# md2_redraw.net
KiCad netlist of a schematic drawn in EAGLE
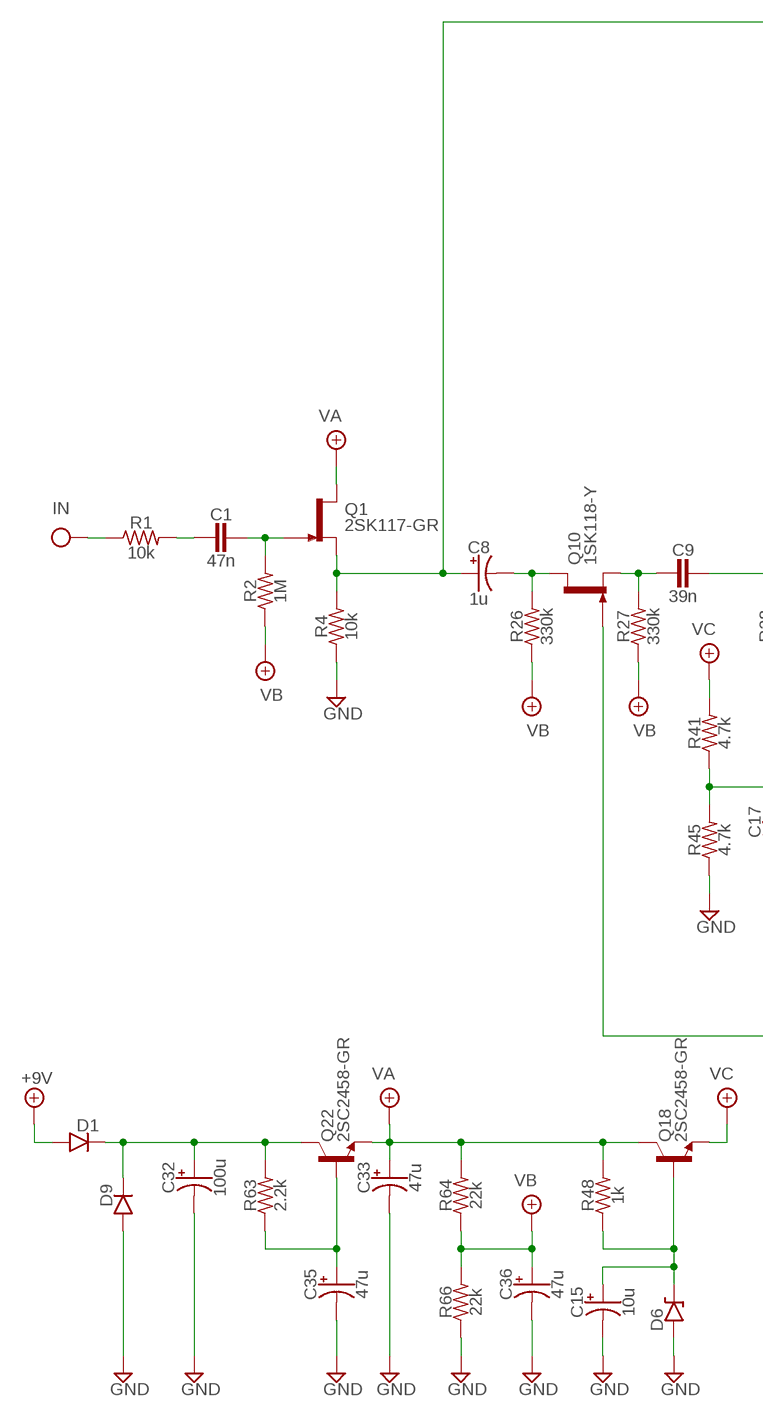
[diagram p0: schematic, sheet 1, part 1 of 2]
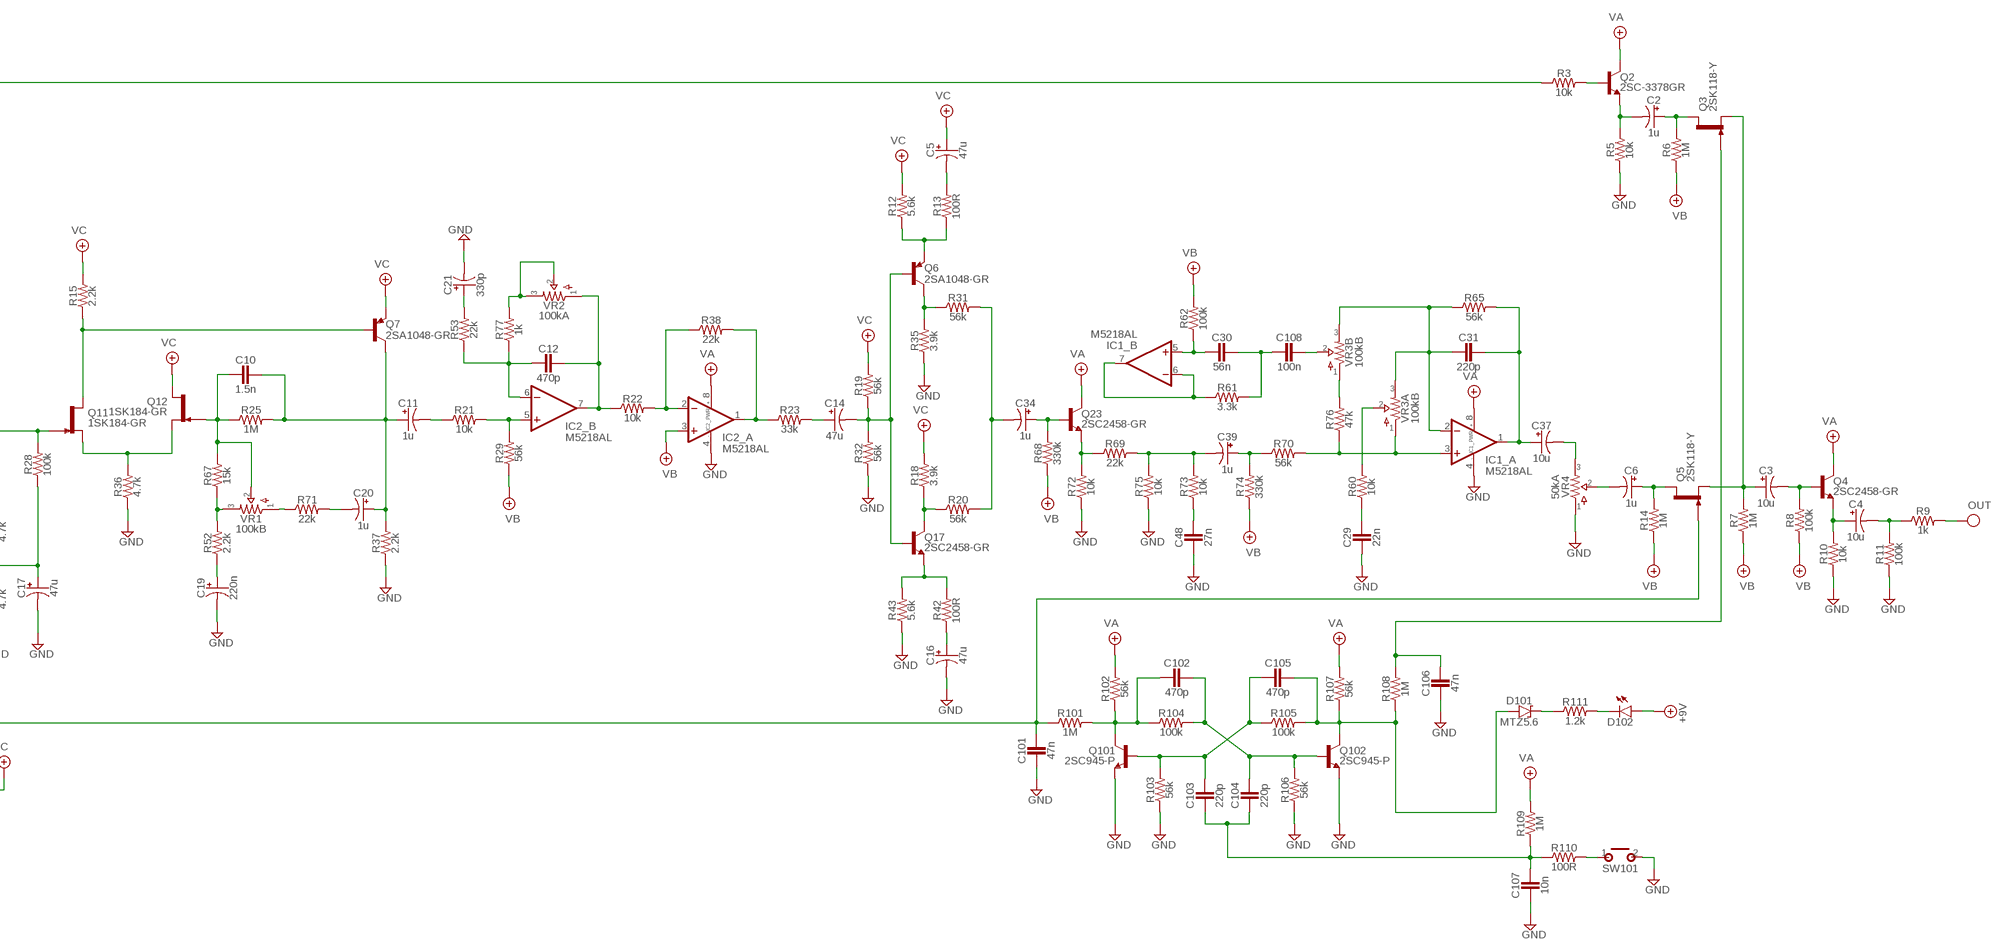
[diagram p1: schematic, sheet 1, part 2 of 2]

(export (version "E")
  (design (tool "Eeschema 10.0.6"))
  (components
    (comp (ref "C1")
      (value "47n")
      (footprint "eagle-import:BOX_SMALL")
      (libsource (lib "eagle-import") (part "CER/FILMBOX.1"))
    )
    (comp (ref "C2")
      (value "1u")
      (footprint "eagle-import:040_020")
      (libsource (lib "eagle-import") (part "0400"))
    )
    (comp (ref "C3")
      (value "10u")
      (footprint "eagle-import:040_020")
      (libsource (lib "eagle-import") (part "0400"))
    )
    (comp (ref "C4")
      (value "10u")
      (footprint "eagle-import:040_020")
      (libsource (lib "eagle-import") (part "0400"))
    )
    (comp (ref "C5")
      (value "47u")
      (footprint "eagle-import:040_020")
      (libsource (lib "eagle-import") (part "0400"))
    )
    (comp (ref "C6")
      (value "1u")
      (footprint "eagle-import:040_020")
      (libsource (lib "eagle-import") (part "0400"))
    )
    (comp (ref "C8")
      (value "1u")
      (footprint "eagle-import:040_020")
      (libsource (lib "eagle-import") (part "0400"))
    )
    (comp (ref "C9")
      (value "39n")
      (footprint "eagle-import:BOX_SMALL")
      (libsource (lib "eagle-import") (part "CER/FILMBOX.1"))
    )
    (comp (ref "C10")
      (value "1.5n")
      (footprint "eagle-import:BOX_SMALL")
      (libsource (lib "eagle-import") (part "CER/FILMBOX.1"))
    )
    (comp (ref "C11")
      (value "1u")
      (footprint "eagle-import:040_020")
      (libsource (lib "eagle-import") (part "0400"))
    )
    (comp (ref "C12")
      (value "470p")
      (footprint "eagle-import:BOX_SMALL")
      (libsource (lib "eagle-import") (part "CER/FILMBOX.1"))
    )
    (comp (ref "C14")
      (value "47u")
      (footprint "eagle-import:040_020")
      (libsource (lib "eagle-import") (part "0400"))
    )
    (comp (ref "C15")
      (value "10u")
      (footprint "eagle-import:040_020")
      (libsource (lib "eagle-import") (part "0400"))
    )
    (comp (ref "C16")
      (value "47u")
      (footprint "eagle-import:040_020")
      (libsource (lib "eagle-import") (part "0400"))
    )
    (comp (ref "C17")
      (value "47u")
      (footprint "eagle-import:040_020")
      (libsource (lib "eagle-import") (part "0400"))
    )
    (comp (ref "C19")
      (value "220n")
      (footprint "eagle-import:040_020")
      (libsource (lib "eagle-import") (part "0400"))
    )
    (comp (ref "C20")
      (value "1u")
      (footprint "eagle-import:040_020")
      (libsource (lib "eagle-import") (part "0400"))
    )
    (comp (ref "C21")
      (value "330p")
      (footprint "eagle-import:040_020")
      (libsource (lib "eagle-import") (part "0400"))
    )
    (comp (ref "C29")
      (value "22n")
      (footprint "eagle-import:BOX_SMALL")
      (libsource (lib "eagle-import") (part "CER/FILMBOX.1"))
    )
    (comp (ref "C30")
      (value "56n")
      (footprint "eagle-import:BOX_SMALL")
      (libsource (lib "eagle-import") (part "CER/FILMBOX.1"))
    )
    (comp (ref "C31")
      (value "220p")
      (footprint "eagle-import:BOX_SMALL")
      (libsource (lib "eagle-import") (part "CER/FILMBOX.1"))
    )
    (comp (ref "C32")
      (value "100u")
      (footprint "eagle-import:040_020")
      (libsource (lib "eagle-import") (part "0400"))
    )
    (comp (ref "C33")
      (value "47u")
      (footprint "eagle-import:040_020")
      (libsource (lib "eagle-import") (part "0400"))
    )
    (comp (ref "C34")
      (value "1u")
      (footprint "eagle-import:040_020")
      (libsource (lib "eagle-import") (part "0400"))
    )
    (comp (ref "C35")
      (value "47u")
      (footprint "eagle-import:040_020")
      (libsource (lib "eagle-import") (part "0400"))
    )
    (comp (ref "C36")
      (value "47u")
      (footprint "eagle-import:040_020")
      (libsource (lib "eagle-import") (part "0400"))
    )
    (comp (ref "C37")
      (value "10u")
      (footprint "eagle-import:040_020")
      (libsource (lib "eagle-import") (part "0400"))
    )
    (comp (ref "C39")
      (value "1u")
      (footprint "eagle-import:040_020")
      (libsource (lib "eagle-import") (part "0400"))
    )
    (comp (ref "C48")
      (value "27n")
      (footprint "eagle-import:BOX_SMALL")
      (libsource (lib "eagle-import") (part "CER/FILMBOX.1"))
    )
    (comp (ref "C101")
      (value "47n")
      (footprint "eagle-import:BOX_SMALL")
      (libsource (lib "eagle-import") (part "CER/FILMBOX.1"))
    )
    (comp (ref "C102")
      (value "470p")
      (footprint "eagle-import:BOX_SMALL")
      (libsource (lib "eagle-import") (part "CER/FILMBOX.1"))
    )
    (comp (ref "C103")
      (value "220p")
      (footprint "eagle-import:BOX_SMALL")
      (libsource (lib "eagle-import") (part "CER/FILMBOX.1"))
    )
    (comp (ref "C104")
      (value "220p")
      (footprint "eagle-import:BOX_SMALL")
      (libsource (lib "eagle-import") (part "CER/FILMBOX.1"))
    )
    (comp (ref "C105")
      (value "470p")
      (footprint "eagle-import:BOX_SMALL")
      (libsource (lib "eagle-import") (part "CER/FILMBOX.1"))
    )
    (comp (ref "C106")
      (value "47n")
      (footprint "eagle-import:BOX_SMALL")
      (libsource (lib "eagle-import") (part "CER/FILMBOX.1"))
    )
    (comp (ref "C107")
      (value "10n")
      (footprint "eagle-import:BOX_SMALL")
      (libsource (lib "eagle-import") (part "CER/FILMBOX.1"))
    )
    (comp (ref "C108")
      (value "100n")
      (footprint "eagle-import:BOX_SMALL")
      (libsource (lib "eagle-import") (part "CER/FILMBOX.1"))
    )
    (comp (ref "D1")
      (value "DO35.2")
      (footprint "eagle-import:DO35-2")
      (libsource (lib "eagle-import") (part "DO35.2"))
    )
    (comp (ref "D6")
      (value "ZENER.2")
      (footprint "eagle-import:DO41-2")
      (libsource (lib "eagle-import") (part "ZENER.2"))
    )
    (comp (ref "D9")
      (value "DO35.2")
      (footprint "eagle-import:DO35-2")
      (libsource (lib "eagle-import") (part "DO35.2"))
    )
    (comp (ref "D101")
      (value "MTZ5.6")
      (footprint "eagle-import:DO41-2")
      (libsource (lib "eagle-import") (part "ZENER.2"))
    )
    (comp (ref "D102")
      (value "LED")
      (footprint "eagle-import:3MM_D")
      (libsource (lib "eagle-import") (part "LED"))
    )
    (comp (ref "IC1")
      (value "M5218AL")
      (footprint "eagle-import:DIL0")
      (libsource (lib "eagle-import") (part "DUALTH"))
    )
    (comp (ref "IC2")
      (value "M5218AL")
      (footprint "eagle-import:DIL0")
      (libsource (lib "eagle-import") (part "DUALTH"))
    )
    (comp (ref "Q1")
      (value "2SK117-GR")
      (footprint "eagle-import:TO92-")
      (libsource (lib "eagle-import") (part "2N3819TO-92S"))
    )
    (comp (ref "Q2")
      (value "2SC-3378GR")
      (footprint "eagle-import:TO92-")
      (libsource (lib "eagle-import") (part "2SC828A"))
    )
    (comp (ref "Q3")
      (value "2SK118-Y")
      (footprint "eagle-import:TO92-")
      (libsource (lib "eagle-import") (part "2N3819TO-92S"))
    )
    (comp (ref "Q4")
      (value "2SC2458-GR")
      (footprint "eagle-import:TO92-")
      (libsource (lib "eagle-import") (part "2SC828A"))
    )
    (comp (ref "Q5")
      (value "2SK118-Y")
      (footprint "eagle-import:TO92-")
      (libsource (lib "eagle-import") (part "2N3819TO-92S"))
    )
    (comp (ref "Q6")
      (value "2SA1048-GR")
      (footprint "eagle-import:TO92")
      (libsource (lib "eagle-import") (part "2N3906"))
    )
    (comp (ref "Q7")
      (value "2SA1048-GR")
      (footprint "eagle-import:TO92")
      (libsource (lib "eagle-import") (part "2N3906"))
    )
    (comp (ref "Q10")
      (value "1SK118-Y")
      (footprint "eagle-import:TO92-")
      (libsource (lib "eagle-import") (part "2N3819TO-92S"))
    )
    (comp (ref "Q11")
      (value "1SK184-GR")
      (footprint "eagle-import:TO92-")
      (libsource (lib "eagle-import") (part "2N3819TO-92S"))
    )
    (comp (ref "Q12")
      (value "1SK184-GR")
      (footprint "eagle-import:TO92-")
      (libsource (lib "eagle-import") (part "2N3819TO-92S"))
    )
    (comp (ref "Q17")
      (value "2SC2458-GR")
      (footprint "eagle-import:TO92-")
      (libsource (lib "eagle-import") (part "2N3904"))
    )
    (comp (ref "Q18")
      (value "2SC2458-GR")
      (footprint "eagle-import:TO92-")
      (libsource (lib "eagle-import") (part "2SC828A"))
    )
    (comp (ref "Q22")
      (value "2SC2458-GR")
      (footprint "eagle-import:TO92-")
      (libsource (lib "eagle-import") (part "2SC828A"))
    )
    (comp (ref "Q23")
      (value "2SC2458-GR")
      (footprint "eagle-import:TO92-")
      (libsource (lib "eagle-import") (part "2N3904"))
    )
    (comp (ref "Q101")
      (value "2SC945-P")
      (footprint "eagle-import:TO92-")
      (libsource (lib "eagle-import") (part "2SC828A"))
    )
    (comp (ref "Q102")
      (value "2SC945-P")
      (footprint "eagle-import:TO92-")
      (libsource (lib "eagle-import") (part "2SC828A"))
    )
    (comp (ref "R1")
      (value "10k")
      (footprint "eagle-import:R0207_3")
      (libsource (lib "eagle-import") (part "R_.3B"))
    )
    (comp (ref "R2")
      (value "1M")
      (footprint "eagle-import:R0207_3")
      (libsource (lib "eagle-import") (part "R_.3B"))
    )
    (comp (ref "R3")
      (value "10k")
      (footprint "eagle-import:R0207_3")
      (libsource (lib "eagle-import") (part "R_.3B"))
    )
    (comp (ref "R4")
      (value "10k")
      (footprint "eagle-import:R0207_3")
      (libsource (lib "eagle-import") (part "R_.3B"))
    )
    (comp (ref "R5")
      (value "10k")
      (footprint "eagle-import:R0207_3")
      (libsource (lib "eagle-import") (part "R_.3B"))
    )
    (comp (ref "R6")
      (value "1M")
      (footprint "eagle-import:R0207_3")
      (libsource (lib "eagle-import") (part "R_.3B"))
    )
    (comp (ref "R7")
      (value "1M")
      (footprint "eagle-import:R0207_3")
      (libsource (lib "eagle-import") (part "R_.3B"))
    )
    (comp (ref "R8")
      (value "100k")
      (footprint "eagle-import:R0207_3")
      (libsource (lib "eagle-import") (part "R_.3B"))
    )
    (comp (ref "R9")
      (value "1k")
      (footprint "eagle-import:R0207_3")
      (libsource (lib "eagle-import") (part "R_.3B"))
    )
    (comp (ref "R10")
      (value "10k")
      (footprint "eagle-import:R0207_3")
      (libsource (lib "eagle-import") (part "R_.3B"))
    )
    (comp (ref "R11")
      (value "100k")
      (footprint "eagle-import:R0207_3")
      (libsource (lib "eagle-import") (part "R_.3B"))
    )
    (comp (ref "R12")
      (value "5.6k")
      (footprint "eagle-import:R0207_3")
      (libsource (lib "eagle-import") (part "R_.3B"))
    )
    (comp (ref "R13")
      (value "100R")
      (footprint "eagle-import:R0207_3")
      (libsource (lib "eagle-import") (part "R_.3B"))
    )
    (comp (ref "R14")
      (value "1M")
      (footprint "eagle-import:R0207_3")
      (libsource (lib "eagle-import") (part "R_.3B"))
    )
    (comp (ref "R15")
      (value "2.2k")
      (footprint "eagle-import:R0207_3")
      (libsource (lib "eagle-import") (part "R_.3B"))
    )
    (comp (ref "R18")
      (value "3.9k")
      (footprint "eagle-import:R0207_3")
      (libsource (lib "eagle-import") (part "R_.3B"))
    )
    (comp (ref "R19")
      (value "56k")
      (footprint "eagle-import:R0207_3")
      (libsource (lib "eagle-import") (part "R_.3B"))
    )
    (comp (ref "R20")
      (value "56k")
      (footprint "eagle-import:R0207_3")
      (libsource (lib "eagle-import") (part "R_.3B"))
    )
    (comp (ref "R21")
      (value "10k")
      (footprint "eagle-import:R0207_3")
      (libsource (lib "eagle-import") (part "R_.3B"))
    )
    (comp (ref "R22")
      (value "10k")
      (footprint "eagle-import:R0207_3")
      (libsource (lib "eagle-import") (part "R_.3B"))
    )
    (comp (ref "R23")
      (value "33k")
      (footprint "eagle-import:R0207_3")
      (libsource (lib "eagle-import") (part "R_.3B"))
    )
    (comp (ref "R25")
      (value "1M")
      (footprint "eagle-import:R0207_3")
      (libsource (lib "eagle-import") (part "R_.3B"))
    )
    (comp (ref "R26")
      (value "330k")
      (footprint "eagle-import:R0207_3")
      (libsource (lib "eagle-import") (part "R_.3B"))
    )
    (comp (ref "R27")
      (value "330k")
      (footprint "eagle-import:R0207_3")
      (libsource (lib "eagle-import") (part "R_.3B"))
    )
    (comp (ref "R28")
      (value "100k")
      (footprint "eagle-import:R0207_3")
      (libsource (lib "eagle-import") (part "R_.3B"))
    )
    (comp (ref "R29")
      (value "56k")
      (footprint "eagle-import:R0207_3")
      (libsource (lib "eagle-import") (part "R_.3B"))
    )
    (comp (ref "R31")
      (value "56k")
      (footprint "eagle-import:R0207_3")
      (libsource (lib "eagle-import") (part "R_.3B"))
    )
    (comp (ref "R32")
      (value "56k")
      (footprint "eagle-import:R0207_3")
      (libsource (lib "eagle-import") (part "R_.3B"))
    )
    (comp (ref "R35")
      (value "3.9k")
      (footprint "eagle-import:R0207_3")
      (libsource (lib "eagle-import") (part "R_.3B"))
    )
    (comp (ref "R36")
      (value "4.7k")
      (footprint "eagle-import:R0207_3")
      (libsource (lib "eagle-import") (part "R_.3B"))
    )
    (comp (ref "R37")
      (value "2.2k")
      (footprint "eagle-import:R0207_3")
      (libsource (lib "eagle-import") (part "R_.3B"))
    )
    (comp (ref "R38")
      (value "22k")
      (footprint "eagle-import:R0207_3")
      (libsource (lib "eagle-import") (part "R_.3B"))
    )
    (comp (ref "R41")
      (value "4.7k")
      (footprint "eagle-import:R0207_3")
      (libsource (lib "eagle-import") (part "R_.3B"))
    )
    (comp (ref "R42")
      (value "100R")
      (footprint "eagle-import:R0207_3")
      (libsource (lib "eagle-import") (part "R_.3B"))
    )
    (comp (ref "R43")
      (value "5.6k")
      (footprint "eagle-import:R0207_3")
      (libsource (lib "eagle-import") (part "R_.3B"))
    )
    (comp (ref "R45")
      (value "4.7k")
      (footprint "eagle-import:R0207_3")
      (libsource (lib "eagle-import") (part "R_.3B"))
    )
    (comp (ref "R48")
      (value "1k")
      (footprint "eagle-import:R0207_3")
      (libsource (lib "eagle-import") (part "R_.3B"))
    )
    (comp (ref "R52")
      (value "2.2k")
      (footprint "eagle-import:R0207_3")
      (libsource (lib "eagle-import") (part "R_.3B"))
    )
    (comp (ref "R53")
      (value "22k")
      (footprint "eagle-import:R0207_3")
      (libsource (lib "eagle-import") (part "R_.3B"))
    )
    (comp (ref "R60")
      (value "10k")
      (footprint "eagle-import:R0207_3")
      (libsource (lib "eagle-import") (part "R_.3B"))
    )
    (comp (ref "R61")
      (value "3.3k")
      (footprint "eagle-import:R0207_3")
      (libsource (lib "eagle-import") (part "R_.3B"))
    )
    (comp (ref "R62")
      (value "100k")
      (footprint "eagle-import:R0207_3")
      (libsource (lib "eagle-import") (part "R_.3B"))
    )
    (comp (ref "R63")
      (value "2.2k")
      (footprint "eagle-import:R0207_3")
      (libsource (lib "eagle-import") (part "R_.3B"))
    )
    (comp (ref "R64")
      (value "22k")
      (footprint "eagle-import:R0207_3")
      (libsource (lib "eagle-import") (part "R_.3B"))
    )
    (comp (ref "R65")
      (value "56k")
      (footprint "eagle-import:R0207_3")
      (libsource (lib "eagle-import") (part "R_.3B"))
    )
    (comp (ref "R66")
      (value "22k")
      (footprint "eagle-import:R0207_3")
      (libsource (lib "eagle-import") (part "R_.3B"))
    )
    (comp (ref "R67")
      (value "15k")
      (footprint "eagle-import:R0207_3")
      (libsource (lib "eagle-import") (part "R_.3B"))
    )
    (comp (ref "R68")
      (value "330k")
      (footprint "eagle-import:R0207_3")
      (libsource (lib "eagle-import") (part "R_.3B"))
    )
    (comp (ref "R69")
      (value "22k")
      (footprint "eagle-import:R0207_3")
      (libsource (lib "eagle-import") (part "R_.3B"))
    )
    (comp (ref "R70")
      (value "56k")
      (footprint "eagle-import:R0207_3")
      (libsource (lib "eagle-import") (part "R_.3B"))
    )
    (comp (ref "R71")
      (value "22k")
      (footprint "eagle-import:R0207_3")
      (libsource (lib "eagle-import") (part "R_.3B"))
    )
    (comp (ref "R72")
      (value "10k")
      (footprint "eagle-import:R0207_3")
      (libsource (lib "eagle-import") (part "R_.3B"))
    )
    (comp (ref "R73")
      (value "10k")
      (footprint "eagle-import:R0207_3")
      (libsource (lib "eagle-import") (part "R_.3B"))
    )
    (comp (ref "R74")
      (value "330k")
      (footprint "eagle-import:R0207_3")
      (libsource (lib "eagle-import") (part "R_.3B"))
    )
    (comp (ref "R75")
      (value "10k")
      (footprint "eagle-import:R0207_3")
      (libsource (lib "eagle-import") (part "R_.3B"))
    )
    (comp (ref "R76")
      (value "47k")
      (footprint "eagle-import:R0207_3")
      (libsource (lib "eagle-import") (part "R_.3B"))
    )
    (comp (ref "R77")
      (value "1k")
      (footprint "eagle-import:R0207_3")
      (libsource (lib "eagle-import") (part "R_.3B"))
    )
    (comp (ref "R101")
      (value "1M")
      (footprint "eagle-import:R0207_3")
      (libsource (lib "eagle-import") (part "R_.3B"))
    )
    (comp (ref "R102")
      (value "56k")
      (footprint "eagle-import:R0207_3")
      (libsource (lib "eagle-import") (part "R_.3B"))
    )
    (comp (ref "R103")
      (value "56k")
      (footprint "eagle-import:R0207_3")
      (libsource (lib "eagle-import") (part "R_.3B"))
    )
    (comp (ref "R104")
      (value "100k")
      (footprint "eagle-import:R0207_3")
      (libsource (lib "eagle-import") (part "R_.3B"))
    )
    (comp (ref "R105")
      (value "100k")
      (footprint "eagle-import:R0207_3")
      (libsource (lib "eagle-import") (part "R_.3B"))
    )
    (comp (ref "R106")
      (value "56k")
      (footprint "eagle-import:R0207_3")
      (libsource (lib "eagle-import") (part "R_.3B"))
    )
    (comp (ref "R107")
      (value "56k")
      (footprint "eagle-import:R0207_3")
      (libsource (lib "eagle-import") (part "R_.3B"))
    )
    (comp (ref "R108")
      (value "1M")
      (footprint "eagle-import:R0207_3")
      (libsource (lib "eagle-import") (part "R_.3B"))
    )
    (comp (ref "R109")
      (value "1M")
      (footprint "eagle-import:R0207_3")
      (libsource (lib "eagle-import") (part "R_.3B"))
    )
    (comp (ref "R110")
      (value "100R")
      (footprint "eagle-import:R0207_3")
      (libsource (lib "eagle-import") (part "R_.3B"))
    )
    (comp (ref "R111")
      (value "1.2k")
      (footprint "eagle-import:R0207_3")
      (libsource (lib "eagle-import") (part "R_.3B"))
    )
    (comp (ref "SW101")
      (value "MOMENTARY")
      (footprint "eagle-import:SPST")
      (libsource (lib "eagle-import") (part "MOMENTARY"))
    )
    (comp (ref "VR1")
      (value "100kB")
      (footprint "eagle-import:16MM")
      (libsource (lib "eagle-import") (part "POTS16MM"))
    )
    (comp (ref "VR2")
      (value "100kA")
      (footprint "eagle-import:16MM")
      (libsource (lib "eagle-import") (part "POTS16MM"))
    )
    (comp (ref "VR3A")
      (value "100kB")
      (footprint "eagle-import:16MM")
      (libsource (lib "eagle-import") (part "POTS16MM"))
    )
    (comp (ref "VR3B")
      (value "100kB")
      (footprint "eagle-import:16MM")
      (libsource (lib "eagle-import") (part "POTS16MM"))
    )
    (comp (ref "VR4")
      (value "50kA")
      (footprint "eagle-import:16MM")
      (libsource (lib "eagle-import") (part "POTS16MM"))
    )
  )
  (nets
    (net (code "1") (name "+9V") (class "Default")
      (node (ref "D1") (pin "A") (pinfunction "A_A") (pintype "passive"))
      (node (ref "D102") (pin "ANODE") (pinfunction "A_ANODE") (pintype "passive"))
    )
    (net (code "2") (name "GND") (class "Default")
      (node (ref "C101") (pin "2") (pinfunction "2_2") (pintype "passive"))
      (node (ref "C106") (pin "2") (pinfunction "2_2") (pintype "passive"))
      (node (ref "C107") (pin "2") (pinfunction "2_2") (pintype "passive"))
      (node (ref "C15") (pin "-") (pinfunction "-_-") (pintype "passive"))
      (node (ref "C16") (pin "-") (pinfunction "-_-") (pintype "passive"))
      (node (ref "C17") (pin "-") (pinfunction "-_-") (pintype "passive"))
      (node (ref "C19") (pin "-") (pinfunction "-_-") (pintype "passive"))
      (node (ref "C21") (pin "-") (pinfunction "-_-") (pintype "passive"))
      (node (ref "C29") (pin "2") (pinfunction "2_2") (pintype "passive"))
      (node (ref "C32") (pin "-") (pinfunction "-_-") (pintype "passive"))
      (node (ref "C33") (pin "-") (pinfunction "-_-") (pintype "passive"))
      (node (ref "C35") (pin "-") (pinfunction "-_-") (pintype "passive"))
      (node (ref "C36") (pin "-") (pinfunction "-_-") (pintype "passive"))
      (node (ref "C48") (pin "2") (pinfunction "2_2") (pintype "passive"))
      (node (ref "D6") (pin "A") (pinfunction "A_A") (pintype "passive"))
      (node (ref "D9") (pin "A") (pinfunction "A_A") (pintype "passive"))
      (node (ref "IC1") (pin "4") (pinfunction "V-_4") (pintype "power_in"))
      (node (ref "IC2") (pin "4") (pinfunction "V-_4") (pintype "power_in"))
      (node (ref "Q101") (pin "3") (pinfunction "E_3") (pintype "passive"))
      (node (ref "Q102") (pin "3") (pinfunction "E_3") (pintype "passive"))
      (node (ref "R10") (pin "1") (pinfunction "1_1") (pintype "passive"))
      (node (ref "R103") (pin "1") (pinfunction "1_1") (pintype "passive"))
      (node (ref "R106") (pin "1") (pinfunction "1_1") (pintype "passive"))
      (node (ref "R11") (pin "1") (pinfunction "1_1") (pintype "passive"))
      (node (ref "R32") (pin "1") (pinfunction "1_1") (pintype "passive"))
      (node (ref "R35") (pin "1") (pinfunction "1_1") (pintype "passive"))
      (node (ref "R36") (pin "1") (pinfunction "1_1") (pintype "passive"))
      (node (ref "R37") (pin "1") (pinfunction "1_1") (pintype "passive"))
      (node (ref "R4") (pin "1") (pinfunction "1_1") (pintype "passive"))
      (node (ref "R43") (pin "1") (pinfunction "1_1") (pintype "passive"))
      (node (ref "R45") (pin "1") (pinfunction "1_1") (pintype "passive"))
      (node (ref "R5") (pin "1") (pinfunction "1_1") (pintype "passive"))
      (node (ref "R66") (pin "1") (pinfunction "1_1") (pintype "passive"))
      (node (ref "R72") (pin "1") (pinfunction "1_1") (pintype "passive"))
      (node (ref "R75") (pin "1") (pinfunction "1_1") (pintype "passive"))
      (node (ref "SW101") (pin "2") (pinfunction "S_2") (pintype "passive"))
      (node (ref "VR4") (pin "1") (pinfunction "1_1") (pintype "passive"))
    )
    (net (code "3") (name "IN") (class "Default")
      (node (ref "R1") (pin "1") (pinfunction "1_1") (pintype "passive"))
    )
    (net (code "4") (name "Net-(C1-Pad2)") (class "Default")
      (node (ref "C1") (pin "2") (pinfunction "2_2") (pintype "passive"))
      (node (ref "R1") (pin "2") (pinfunction "2_2") (pintype "passive"))
    )
    (net (code "5") (name "Net-(C4-Pad-)") (class "Default")
      (node (ref "C4") (pin "-") (pinfunction "-_-") (pintype "passive"))
      (node (ref "R11") (pin "2") (pinfunction "2_2") (pintype "passive"))
      (node (ref "R9") (pin "1") (pinfunction "1_1") (pintype "passive"))
    )
    (net (code "6") (name "Net-(C5-Pad-)") (class "Default")
      (node (ref "C5") (pin "-") (pinfunction "-_-") (pintype "passive"))
      (node (ref "R13") (pin "2") (pinfunction "2_2") (pintype "passive"))
    )
    (net (code "7") (name "Net-(C6-Pad-)") (class "Default")
      (node (ref "C6") (pin "-") (pinfunction "-_-") (pintype "passive"))
      (node (ref "VR4") (pin "2") (pinfunction "2_2") (pintype "passive"))
    )
    (net (code "8") (name "Net-(C11-Pad-)") (class "Default")
      (node (ref "C11") (pin "-") (pinfunction "-_-") (pintype "passive"))
      (node (ref "R21") (pin "1") (pinfunction "1_1") (pintype "passive"))
    )
    (net (code "9") (name "Net-(C14-Pad+)") (class "Default")
      (node (ref "C14") (pin "+") (pinfunction "+_+") (pintype "passive"))
      (node (ref "R23") (pin "2") (pinfunction "2_2") (pintype "passive"))
    )
    (net (code "10") (name "Net-(C16-Pad+)") (class "Default")
      (node (ref "C16") (pin "+") (pinfunction "+_+") (pintype "passive"))
      (node (ref "R42") (pin "1") (pinfunction "1_1") (pintype "passive"))
    )
    (net (code "11") (name "Net-(C17-Pad+)") (class "Default")
      (node (ref "C17") (pin "+") (pinfunction "+_+") (pintype "passive"))
      (node (ref "R28") (pin "1") (pinfunction "1_1") (pintype "passive"))
      (node (ref "R41") (pin "1") (pinfunction "1_1") (pintype "passive"))
      (node (ref "R45") (pin "2") (pinfunction "2_2") (pintype "passive"))
    )
    (net (code "12") (name "Net-(C19-Pad+)") (class "Default")
      (node (ref "C19") (pin "+") (pinfunction "+_+") (pintype "passive"))
      (node (ref "R52") (pin "1") (pinfunction "1_1") (pintype "passive"))
    )
    (net (code "13") (name "Net-(C20-Pad-)") (class "Default")
      (node (ref "C20") (pin "-") (pinfunction "-_-") (pintype "passive"))
      (node (ref "R71") (pin "2") (pinfunction "2_2") (pintype "passive"))
    )
    (net (code "14") (name "Net-(C21-Pad+)") (class "Default")
      (node (ref "C21") (pin "+") (pinfunction "+_+") (pintype "passive"))
      (node (ref "R53") (pin "2") (pinfunction "2_2") (pintype "passive"))
    )
    (net (code "15") (name "Net-(C29-Pad1)") (class "Default")
      (node (ref "C29") (pin "1") (pinfunction "1_1") (pintype "passive"))
      (node (ref "R60") (pin "1") (pinfunction "1_1") (pintype "passive"))
    )
    (net (code "16") (name "Net-(C34-Pad-)") (class "Default")
      (node (ref "C34") (pin "-") (pinfunction "-_-") (pintype "passive"))
      (node (ref "R20") (pin "2") (pinfunction "2_2") (pintype "passive"))
      (node (ref "R31") (pin "2") (pinfunction "2_2") (pintype "passive"))
    )
    (net (code "17") (name "Net-(C37-Pad-)") (class "Default")
      (node (ref "C37") (pin "-") (pinfunction "-_-") (pintype "passive"))
      (node (ref "VR4") (pin "3") (pinfunction "3_3") (pintype "passive"))
    )
    (net (code "18") (name "Net-(C39-Pad+)") (class "Default")
      (node (ref "C39") (pin "+") (pinfunction "+_+") (pintype "passive"))
      (node (ref "R70") (pin "1") (pinfunction "1_1") (pintype "passive"))
      (node (ref "R74") (pin "2") (pinfunction "2_2") (pintype "passive"))
    )
    (net (code "19") (name "Net-(C39-Pad-)") (class "Default")
      (node (ref "C39") (pin "-") (pinfunction "-_-") (pintype "passive"))
      (node (ref "R69") (pin "2") (pinfunction "2_2") (pintype "passive"))
      (node (ref "R73") (pin "2") (pinfunction "2_2") (pintype "passive"))
      (node (ref "R75") (pin "2") (pinfunction "2_2") (pintype "passive"))
    )
    (net (code "20") (name "Net-(C48-Pad1)") (class "Default")
      (node (ref "C48") (pin "1") (pinfunction "1_1") (pintype "passive"))
      (node (ref "R73") (pin "1") (pinfunction "1_1") (pintype "passive"))
    )
    (net (code "21") (name "Net-(C103-Pad2)") (class "Default")
      (node (ref "C103") (pin "2") (pinfunction "2_2") (pintype "passive"))
      (node (ref "C104") (pin "2") (pinfunction "2_2") (pintype "passive"))
      (node (ref "C107") (pin "1") (pinfunction "1_1") (pintype "passive"))
      (node (ref "R109") (pin "1") (pinfunction "1_1") (pintype "passive"))
      (node (ref "R110") (pin "1") (pinfunction "1_1") (pintype "passive"))
    )
    (net (code "22") (name "Net-(C108-Pad1)") (class "Default")
      (node (ref "C108") (pin "1") (pinfunction "1_1") (pintype "passive"))
      (node (ref "VR3B") (pin "2") (pinfunction "2_2") (pintype "passive"))
    )
    (net (code "23") (name "Net-(C108-Pad2)") (class "Default")
      (node (ref "C108") (pin "2") (pinfunction "2_2") (pintype "passive"))
      (node (ref "C30") (pin "1") (pinfunction "1_1") (pintype "passive"))
      (node (ref "R61") (pin "2") (pinfunction "2_2") (pintype "passive"))
    )
    (net (code "24") (name "Net-(D101-PadC)") (class "Default")
      (node (ref "D101") (pin "C") (pinfunction "C_C") (pintype "passive"))
      (node (ref "R111") (pin "1") (pinfunction "1_1") (pintype "passive"))
    )
    (net (code "25") (name "Net-(D102-C)") (class "Default")
      (node (ref "D102") (pin "P$1") (pinfunction "C_P$1") (pintype "passive"))
      (node (ref "R111") (pin "2") (pinfunction "2_2") (pintype "passive"))
    )
    (net (code "26") (name "Net-(IC1A-+IN)") (class "Default")
      (node (ref "IC1") (pin "3") (pinfunction "+IN_3") (pintype "input"))
      (node (ref "R70") (pin "2") (pinfunction "2_2") (pintype "passive"))
      (node (ref "R76") (pin "1") (pinfunction "1_1") (pintype "passive"))
      (node (ref "VR3A") (pin "1") (pinfunction "1_1") (pintype "passive"))
    )
    (net (code "27") (name "Net-(IC1A--IN)") (class "Default")
      (node (ref "C31") (pin "2") (pinfunction "2_2") (pintype "passive"))
      (node (ref "IC1") (pin "2") (pinfunction "-IN_2") (pintype "input"))
      (node (ref "R65") (pin "1") (pinfunction "1_1") (pintype "passive"))
      (node (ref "VR3A") (pin "3") (pinfunction "3_3") (pintype "passive"))
      (node (ref "VR3B") (pin "3") (pinfunction "3_3") (pintype "passive"))
    )
    (net (code "28") (name "Net-(IC1A-OUT)") (class "Default")
      (node (ref "C31") (pin "1") (pinfunction "1_1") (pintype "passive"))
      (node (ref "C37") (pin "+") (pinfunction "+_+") (pintype "passive"))
      (node (ref "IC1") (pin "1") (pinfunction "OUT_1") (pintype "output"))
      (node (ref "R65") (pin "2") (pinfunction "2_2") (pintype "passive"))
    )
    (net (code "29") (name "Net-(IC1B-+IN)") (class "Default")
      (node (ref "C30") (pin "2") (pinfunction "2_2") (pintype "passive"))
      (node (ref "IC1") (pin "5") (pinfunction "+IN_5") (pintype "input"))
      (node (ref "R62") (pin "1") (pinfunction "1_1") (pintype "passive"))
    )
    (net (code "30") (name "Net-(IC1B--IN)") (class "Default")
      (node (ref "IC1") (pin "6") (pinfunction "-IN_6") (pintype "input"))
      (node (ref "IC1") (pin "7") (pinfunction "OUT_7") (pintype "output"))
      (node (ref "R61") (pin "1") (pinfunction "1_1") (pintype "passive"))
    )
    (net (code "31") (name "Net-(IC2A--IN)") (class "Default")
      (node (ref "IC2") (pin "2") (pinfunction "-IN_2") (pintype "input"))
      (node (ref "R22") (pin "2") (pinfunction "2_2") (pintype "passive"))
      (node (ref "R38") (pin "1") (pinfunction "1_1") (pintype "passive"))
    )
    (net (code "32") (name "Net-(IC2A-OUT)") (class "Default")
      (node (ref "IC2") (pin "1") (pinfunction "OUT_1") (pintype "output"))
      (node (ref "R23") (pin "1") (pinfunction "1_1") (pintype "passive"))
      (node (ref "R38") (pin "2") (pinfunction "2_2") (pintype "passive"))
    )
    (net (code "33") (name "Net-(IC2B-+IN)") (class "Default")
      (node (ref "IC2") (pin "5") (pinfunction "+IN_5") (pintype "input"))
      (node (ref "R21") (pin "2") (pinfunction "2_2") (pintype "passive"))
      (node (ref "R29") (pin "2") (pinfunction "2_2") (pintype "passive"))
    )
    (net (code "34") (name "Net-(IC2B--IN)") (class "Default")
      (node (ref "C12") (pin "2") (pinfunction "2_2") (pintype "passive"))
      (node (ref "IC2") (pin "6") (pinfunction "-IN_6") (pintype "input"))
      (node (ref "R53") (pin "1") (pinfunction "1_1") (pintype "passive"))
      (node (ref "R77") (pin "1") (pinfunction "1_1") (pintype "passive"))
    )
    (net (code "35") (name "Net-(IC2B-OUT)") (class "Default")
      (node (ref "C12") (pin "1") (pinfunction "1_1") (pintype "passive"))
      (node (ref "IC2") (pin "7") (pinfunction "OUT_7") (pintype "output"))
      (node (ref "R22") (pin "1") (pinfunction "1_1") (pintype "passive"))
      (node (ref "VR2") (pin "1") (pinfunction "1_1") (pintype "passive"))
    )
    (net (code "36") (name "Net-(Q1-G)") (class "Default")
      (node (ref "C1") (pin "1") (pinfunction "1_1") (pintype "passive"))
      (node (ref "Q1") (pin "2") (pinfunction "G_2") (pintype "passive"))
      (node (ref "R2") (pin "2") (pinfunction "2_2") (pintype "passive"))
    )
    (net (code "37") (name "Net-(Q1-S)") (class "Default")
      (node (ref "C8") (pin "+") (pinfunction "+_+") (pintype "passive"))
      (node (ref "Q1") (pin "1") (pinfunction "S_1") (pintype "passive"))
      (node (ref "R3") (pin "1") (pinfunction "1_1") (pintype "passive"))
      (node (ref "R4") (pin "2") (pinfunction "2_2") (pintype "passive"))
    )
    (net (code "38") (name "Net-(Q2-B)") (class "Default")
      (node (ref "Q2") (pin "1") (pinfunction "B_1") (pintype "passive"))
      (node (ref "R3") (pin "2") (pinfunction "2_2") (pintype "passive"))
    )
    (net (code "39") (name "Net-(Q2-E)") (class "Default")
      (node (ref "C2") (pin "-") (pinfunction "-_-") (pintype "passive"))
      (node (ref "Q2") (pin "3") (pinfunction "E_3") (pintype "passive"))
      (node (ref "R5") (pin "2") (pinfunction "2_2") (pintype "passive"))
    )
    (net (code "40") (name "Net-(Q3-D)") (class "Default")
      (node (ref "C2") (pin "+") (pinfunction "+_+") (pintype "passive"))
      (node (ref "Q3") (pin "3") (pinfunction "D_3") (pintype "passive"))
      (node (ref "R6") (pin "2") (pinfunction "2_2") (pintype "passive"))
    )
    (net (code "41") (name "Net-(Q3-G)") (class "Default")
      (node (ref "C106") (pin "1") (pinfunction "1_1") (pintype "passive"))
      (node (ref "Q3") (pin "2") (pinfunction "G_2") (pintype "passive"))
      (node (ref "R108") (pin "2") (pinfunction "2_2") (pintype "passive"))
    )
    (net (code "42") (name "Net-(Q3-S)") (class "Default")
      (node (ref "C3") (pin "+") (pinfunction "+_+") (pintype "passive"))
      (node (ref "Q3") (pin "1") (pinfunction "S_1") (pintype "passive"))
      (node (ref "Q5") (pin "1") (pinfunction "S_1") (pintype "passive"))
      (node (ref "R7") (pin "2") (pinfunction "2_2") (pintype "passive"))
    )
    (net (code "43") (name "Net-(Q4-B)") (class "Default")
      (node (ref "C3") (pin "-") (pinfunction "-_-") (pintype "passive"))
      (node (ref "Q4") (pin "1") (pinfunction "B_1") (pintype "passive"))
      (node (ref "R8") (pin "2") (pinfunction "2_2") (pintype "passive"))
    )
    (net (code "44") (name "Net-(Q4-E)") (class "Default")
      (node (ref "C4") (pin "+") (pinfunction "+_+") (pintype "passive"))
      (node (ref "Q4") (pin "3") (pinfunction "E_3") (pintype "passive"))
      (node (ref "R10") (pin "2") (pinfunction "2_2") (pintype "passive"))
    )
    (net (code "45") (name "Net-(Q5-D)") (class "Default")
      (node (ref "C6") (pin "+") (pinfunction "+_+") (pintype "passive"))
      (node (ref "Q5") (pin "3") (pinfunction "D_3") (pintype "passive"))
      (node (ref "R14") (pin "2") (pinfunction "2_2") (pintype "passive"))
    )
    (net (code "46") (name "Net-(Q6-C)") (class "Default")
      (node (ref "Q6") (pin "1") (pinfunction "C_1") (pintype "passive"))
      (node (ref "R31") (pin "1") (pinfunction "1_1") (pintype "passive"))
      (node (ref "R35") (pin "2") (pinfunction "2_2") (pintype "passive"))
    )
    (net (code "47") (name "Net-(Q6-E)") (class "Default")
      (node (ref "Q6") (pin "3") (pinfunction "E_3") (pintype "passive"))
      (node (ref "R12") (pin "1") (pinfunction "1_1") (pintype "passive"))
      (node (ref "R13") (pin "1") (pinfunction "1_1") (pintype "passive"))
    )
    (net (code "48") (name "Net-(Q7-C)") (class "Default")
      (node (ref "C10") (pin "1") (pinfunction "1_1") (pintype "passive"))
      (node (ref "C11") (pin "+") (pinfunction "+_+") (pintype "passive"))
      (node (ref "C20") (pin "+") (pinfunction "+_+") (pintype "passive"))
      (node (ref "Q7") (pin "1") (pinfunction "C_1") (pintype "passive"))
      (node (ref "R25") (pin "2") (pinfunction "2_2") (pintype "passive"))
      (node (ref "R37") (pin "2") (pinfunction "2_2") (pintype "passive"))
    )
    (net (code "49") (name "Net-(Q10-D)") (class "Default")
      (node (ref "C8") (pin "-") (pinfunction "-_-") (pintype "passive"))
      (node (ref "Q10") (pin "3") (pinfunction "D_3") (pintype "passive"))
      (node (ref "R26") (pin "2") (pinfunction "2_2") (pintype "passive"))
    )
    (net (code "50") (name "Net-(Q10-G)") (class "Default")
      (node (ref "C101") (pin "1") (pinfunction "1_1") (pintype "passive"))
      (node (ref "Q10") (pin "2") (pinfunction "G_2") (pintype "passive"))
      (node (ref "Q5") (pin "2") (pinfunction "G_2") (pintype "passive"))
      (node (ref "R101") (pin "1") (pinfunction "1_1") (pintype "passive"))
    )
    (net (code "51") (name "Net-(Q10-S)") (class "Default")
      (node (ref "C9") (pin "2") (pinfunction "2_2") (pintype "passive"))
      (node (ref "Q10") (pin "1") (pinfunction "S_1") (pintype "passive"))
      (node (ref "R27") (pin "2") (pinfunction "2_2") (pintype "passive"))
    )
    (net (code "52") (name "Net-(Q11-D)") (class "Default")
      (node (ref "Q11") (pin "3") (pinfunction "D_3") (pintype "passive"))
      (node (ref "Q7") (pin "2") (pinfunction "B_2") (pintype "passive"))
      (node (ref "R15") (pin "1") (pinfunction "1_1") (pintype "passive"))
    )
    (net (code "53") (name "Net-(Q11-G)") (class "Default")
      (node (ref "C9") (pin "1") (pinfunction "1_1") (pintype "passive"))
      (node (ref "Q11") (pin "2") (pinfunction "G_2") (pintype "passive"))
      (node (ref "R28") (pin "2") (pinfunction "2_2") (pintype "passive"))
    )
    (net (code "54") (name "Net-(Q11-S)") (class "Default")
      (node (ref "Q11") (pin "1") (pinfunction "S_1") (pintype "passive"))
      (node (ref "Q12") (pin "1") (pinfunction "S_1") (pintype "passive"))
      (node (ref "R36") (pin "2") (pinfunction "2_2") (pintype "passive"))
    )
    (net (code "55") (name "Net-(Q12-G)") (class "Default")
      (node (ref "C10") (pin "2") (pinfunction "2_2") (pintype "passive"))
      (node (ref "Q12") (pin "2") (pinfunction "G_2") (pintype "passive"))
      (node (ref "R25") (pin "1") (pinfunction "1_1") (pintype "passive"))
      (node (ref "R67") (pin "2") (pinfunction "2_2") (pintype "passive"))
      (node (ref "VR1") (pin "2") (pinfunction "2_2") (pintype "passive"))
    )
    (net (code "56") (name "Net-(Q17-B)") (class "Default")
      (node (ref "C14") (pin "-") (pinfunction "-_-") (pintype "passive"))
      (node (ref "Q17") (pin "2") (pinfunction "B_2") (pintype "passive"))
      (node (ref "Q6") (pin "2") (pinfunction "B_2") (pintype "passive"))
      (node (ref "R19") (pin "1") (pinfunction "1_1") (pintype "passive"))
      (node (ref "R32") (pin "2") (pinfunction "2_2") (pintype "passive"))
    )
    (net (code "57") (name "Net-(Q17-C)") (class "Default")
      (node (ref "Q17") (pin "1") (pinfunction "C_1") (pintype "passive"))
      (node (ref "R18") (pin "1") (pinfunction "1_1") (pintype "passive"))
      (node (ref "R20") (pin "1") (pinfunction "1_1") (pintype "passive"))
    )
    (net (code "58") (name "Net-(Q17-E)") (class "Default")
      (node (ref "Q17") (pin "3") (pinfunction "E_3") (pintype "passive"))
      (node (ref "R42") (pin "2") (pinfunction "2_2") (pintype "passive"))
      (node (ref "R43") (pin "2") (pinfunction "2_2") (pintype "passive"))
    )
    (net (code "59") (name "Net-(Q18-B)") (class "Default")
      (node (ref "C15") (pin "+") (pinfunction "+_+") (pintype "passive"))
      (node (ref "D6") (pin "C") (pinfunction "C_C") (pintype "passive"))
      (node (ref "Q18") (pin "1") (pinfunction "B_1") (pintype "passive"))
      (node (ref "R48") (pin "1") (pinfunction "1_1") (pintype "passive"))
    )
    (net (code "60") (name "Net-(Q22-B)") (class "Default")
      (node (ref "C35") (pin "+") (pinfunction "+_+") (pintype "passive"))
      (node (ref "Q22") (pin "1") (pinfunction "B_1") (pintype "passive"))
      (node (ref "R63") (pin "1") (pinfunction "1_1") (pintype "passive"))
    )
    (net (code "61") (name "Net-(Q22-C)") (class "Default")
      (node (ref "C32") (pin "+") (pinfunction "+_+") (pintype "passive"))
      (node (ref "D1") (pin "C") (pinfunction "C_C") (pintype "passive"))
      (node (ref "D9") (pin "C") (pinfunction "C_C") (pintype "passive"))
      (node (ref "Q22") (pin "2") (pinfunction "C_2") (pintype "passive"))
      (node (ref "R63") (pin "2") (pinfunction "2_2") (pintype "passive"))
    )
    (net (code "62") (name "Net-(Q23-B)") (class "Default")
      (node (ref "C34") (pin "+") (pinfunction "+_+") (pintype "passive"))
      (node (ref "Q23") (pin "2") (pinfunction "B_2") (pintype "passive"))
      (node (ref "R68") (pin "2") (pinfunction "2_2") (pintype "passive"))
    )
    (net (code "63") (name "Net-(Q23-E)") (class "Default")
      (node (ref "Q23") (pin "3") (pinfunction "E_3") (pintype "passive"))
      (node (ref "R69") (pin "1") (pinfunction "1_1") (pintype "passive"))
      (node (ref "R72") (pin "2") (pinfunction "2_2") (pintype "passive"))
    )
    (net (code "64") (name "Net-(Q101-B)") (class "Default")
      (node (ref "C103") (pin "1") (pinfunction "1_1") (pintype "passive"))
      (node (ref "C105") (pin "2") (pinfunction "2_2") (pintype "passive"))
      (node (ref "Q101") (pin "1") (pinfunction "B_1") (pintype "passive"))
      (node (ref "R103") (pin "2") (pinfunction "2_2") (pintype "passive"))
      (node (ref "R105") (pin "1") (pinfunction "1_1") (pintype "passive"))
    )
    (net (code "65") (name "Net-(Q101-C)") (class "Default")
      (node (ref "C102") (pin "2") (pinfunction "2_2") (pintype "passive"))
      (node (ref "Q101") (pin "2") (pinfunction "C_2") (pintype "passive"))
      (node (ref "R101") (pin "2") (pinfunction "2_2") (pintype "passive"))
      (node (ref "R102") (pin "1") (pinfunction "1_1") (pintype "passive"))
      (node (ref "R104") (pin "1") (pinfunction "1_1") (pintype "passive"))
    )
    (net (code "66") (name "Net-(Q102-B)") (class "Default")
      (node (ref "C102") (pin "1") (pinfunction "1_1") (pintype "passive"))
      (node (ref "C104") (pin "1") (pinfunction "1_1") (pintype "passive"))
      (node (ref "Q102") (pin "1") (pinfunction "B_1") (pintype "passive"))
      (node (ref "R104") (pin "2") (pinfunction "2_2") (pintype "passive"))
      (node (ref "R106") (pin "2") (pinfunction "2_2") (pintype "passive"))
    )
    (net (code "67") (name "Net-(Q102-C)") (class "Default")
      (node (ref "C105") (pin "1") (pinfunction "1_1") (pintype "passive"))
      (node (ref "D101") (pin "A") (pinfunction "A_A") (pintype "passive"))
      (node (ref "Q102") (pin "2") (pinfunction "C_2") (pintype "passive"))
      (node (ref "R105") (pin "2") (pinfunction "2_2") (pintype "passive"))
      (node (ref "R107") (pin "1") (pinfunction "1_1") (pintype "passive"))
      (node (ref "R108") (pin "1") (pinfunction "1_1") (pintype "passive"))
    )
    (net (code "68") (name "Net-(R52-Pad2)") (class "Default")
      (node (ref "R52") (pin "2") (pinfunction "2_2") (pintype "passive"))
      (node (ref "R67") (pin "1") (pinfunction "1_1") (pintype "passive"))
      (node (ref "VR1") (pin "3") (pinfunction "3_3") (pintype "passive"))
    )
    (net (code "69") (name "Net-(R60-Pad2)") (class "Default")
      (node (ref "R60") (pin "2") (pinfunction "2_2") (pintype "passive"))
      (node (ref "VR3A") (pin "2") (pinfunction "2_2") (pintype "passive"))
    )
    (net (code "70") (name "Net-(R71-Pad1)") (class "Default")
      (node (ref "R71") (pin "1") (pinfunction "1_1") (pintype "passive"))
      (node (ref "VR1") (pin "1") (pinfunction "1_1") (pintype "passive"))
    )
    (net (code "71") (name "Net-(R76-Pad2)") (class "Default")
      (node (ref "R76") (pin "2") (pinfunction "2_2") (pintype "passive"))
      (node (ref "VR3B") (pin "1") (pinfunction "1_1") (pintype "passive"))
    )
    (net (code "72") (name "Net-(R77-Pad2)") (class "Default")
      (node (ref "R77") (pin "2") (pinfunction "2_2") (pintype "passive"))
      (node (ref "VR2") (pin "2") (pinfunction "2_2") (pintype "passive"))
      (node (ref "VR2") (pin "3") (pinfunction "3_3") (pintype "passive"))
    )
    (net (code "73") (name "Net-(SW101-P)") (class "Default")
      (node (ref "R110") (pin "2") (pinfunction "2_2") (pintype "passive"))
      (node (ref "SW101") (pin "1") (pinfunction "P_1") (pintype "passive"))
    )
    (net (code "74") (name "OUT") (class "Default")
      (node (ref "R9") (pin "2") (pinfunction "2_2") (pintype "passive"))
    )
    (net (code "75") (name "VA") (class "Default")
      (node (ref "C33") (pin "+") (pinfunction "+_+") (pintype "passive"))
      (node (ref "IC1") (pin "8") (pinfunction "V+_8") (pintype "power_in"))
      (node (ref "IC2") (pin "8") (pinfunction "V+_8") (pintype "power_in"))
      (node (ref "Q1") (pin "3") (pinfunction "D_3") (pintype "passive"))
      (node (ref "Q18") (pin "2") (pinfunction "C_2") (pintype "passive"))
      (node (ref "Q2") (pin "2") (pinfunction "C_2") (pintype "passive"))
      (node (ref "Q22") (pin "3") (pinfunction "E_3") (pintype "passive"))
      (node (ref "Q23") (pin "1") (pinfunction "C_1") (pintype "passive"))
      (node (ref "Q4") (pin "2") (pinfunction "C_2") (pintype "passive"))
      (node (ref "R102") (pin "2") (pinfunction "2_2") (pintype "passive"))
      (node (ref "R107") (pin "2") (pinfunction "2_2") (pintype "passive"))
      (node (ref "R109") (pin "2") (pinfunction "2_2") (pintype "passive"))
      (node (ref "R48") (pin "2") (pinfunction "2_2") (pintype "passive"))
      (node (ref "R64") (pin "2") (pinfunction "2_2") (pintype "passive"))
    )
    (net (code "76") (name "VB") (class "Default")
      (node (ref "C36") (pin "+") (pinfunction "+_+") (pintype "passive"))
      (node (ref "IC2") (pin "3") (pinfunction "+IN_3") (pintype "input"))
      (node (ref "R14") (pin "1") (pinfunction "1_1") (pintype "passive"))
      (node (ref "R2") (pin "1") (pinfunction "1_1") (pintype "passive"))
      (node (ref "R26") (pin "1") (pinfunction "1_1") (pintype "passive"))
      (node (ref "R27") (pin "1") (pinfunction "1_1") (pintype "passive"))
      (node (ref "R29") (pin "1") (pinfunction "1_1") (pintype "passive"))
      (node (ref "R6") (pin "1") (pinfunction "1_1") (pintype "passive"))
      (node (ref "R62") (pin "2") (pinfunction "2_2") (pintype "passive"))
      (node (ref "R64") (pin "1") (pinfunction "1_1") (pintype "passive"))
      (node (ref "R66") (pin "2") (pinfunction "2_2") (pintype "passive"))
      (node (ref "R68") (pin "1") (pinfunction "1_1") (pintype "passive"))
      (node (ref "R7") (pin "1") (pinfunction "1_1") (pintype "passive"))
      (node (ref "R74") (pin "1") (pinfunction "1_1") (pintype "passive"))
      (node (ref "R8") (pin "1") (pinfunction "1_1") (pintype "passive"))
    )
    (net (code "77") (name "VC") (class "Default")
      (node (ref "C5") (pin "+") (pinfunction "+_+") (pintype "passive"))
      (node (ref "Q12") (pin "3") (pinfunction "D_3") (pintype "passive"))
      (node (ref "Q18") (pin "3") (pinfunction "E_3") (pintype "passive"))
      (node (ref "Q7") (pin "3") (pinfunction "E_3") (pintype "passive"))
      (node (ref "R12") (pin "2") (pinfunction "2_2") (pintype "passive"))
      (node (ref "R15") (pin "2") (pinfunction "2_2") (pintype "passive"))
      (node (ref "R18") (pin "2") (pinfunction "2_2") (pintype "passive"))
      (node (ref "R19") (pin "2") (pinfunction "2_2") (pintype "passive"))
      (node (ref "R41") (pin "2") (pinfunction "2_2") (pintype "passive"))
    )
  )
)
